# top_level.net
KiCad netlist of a schematic drawn in Altium Designer
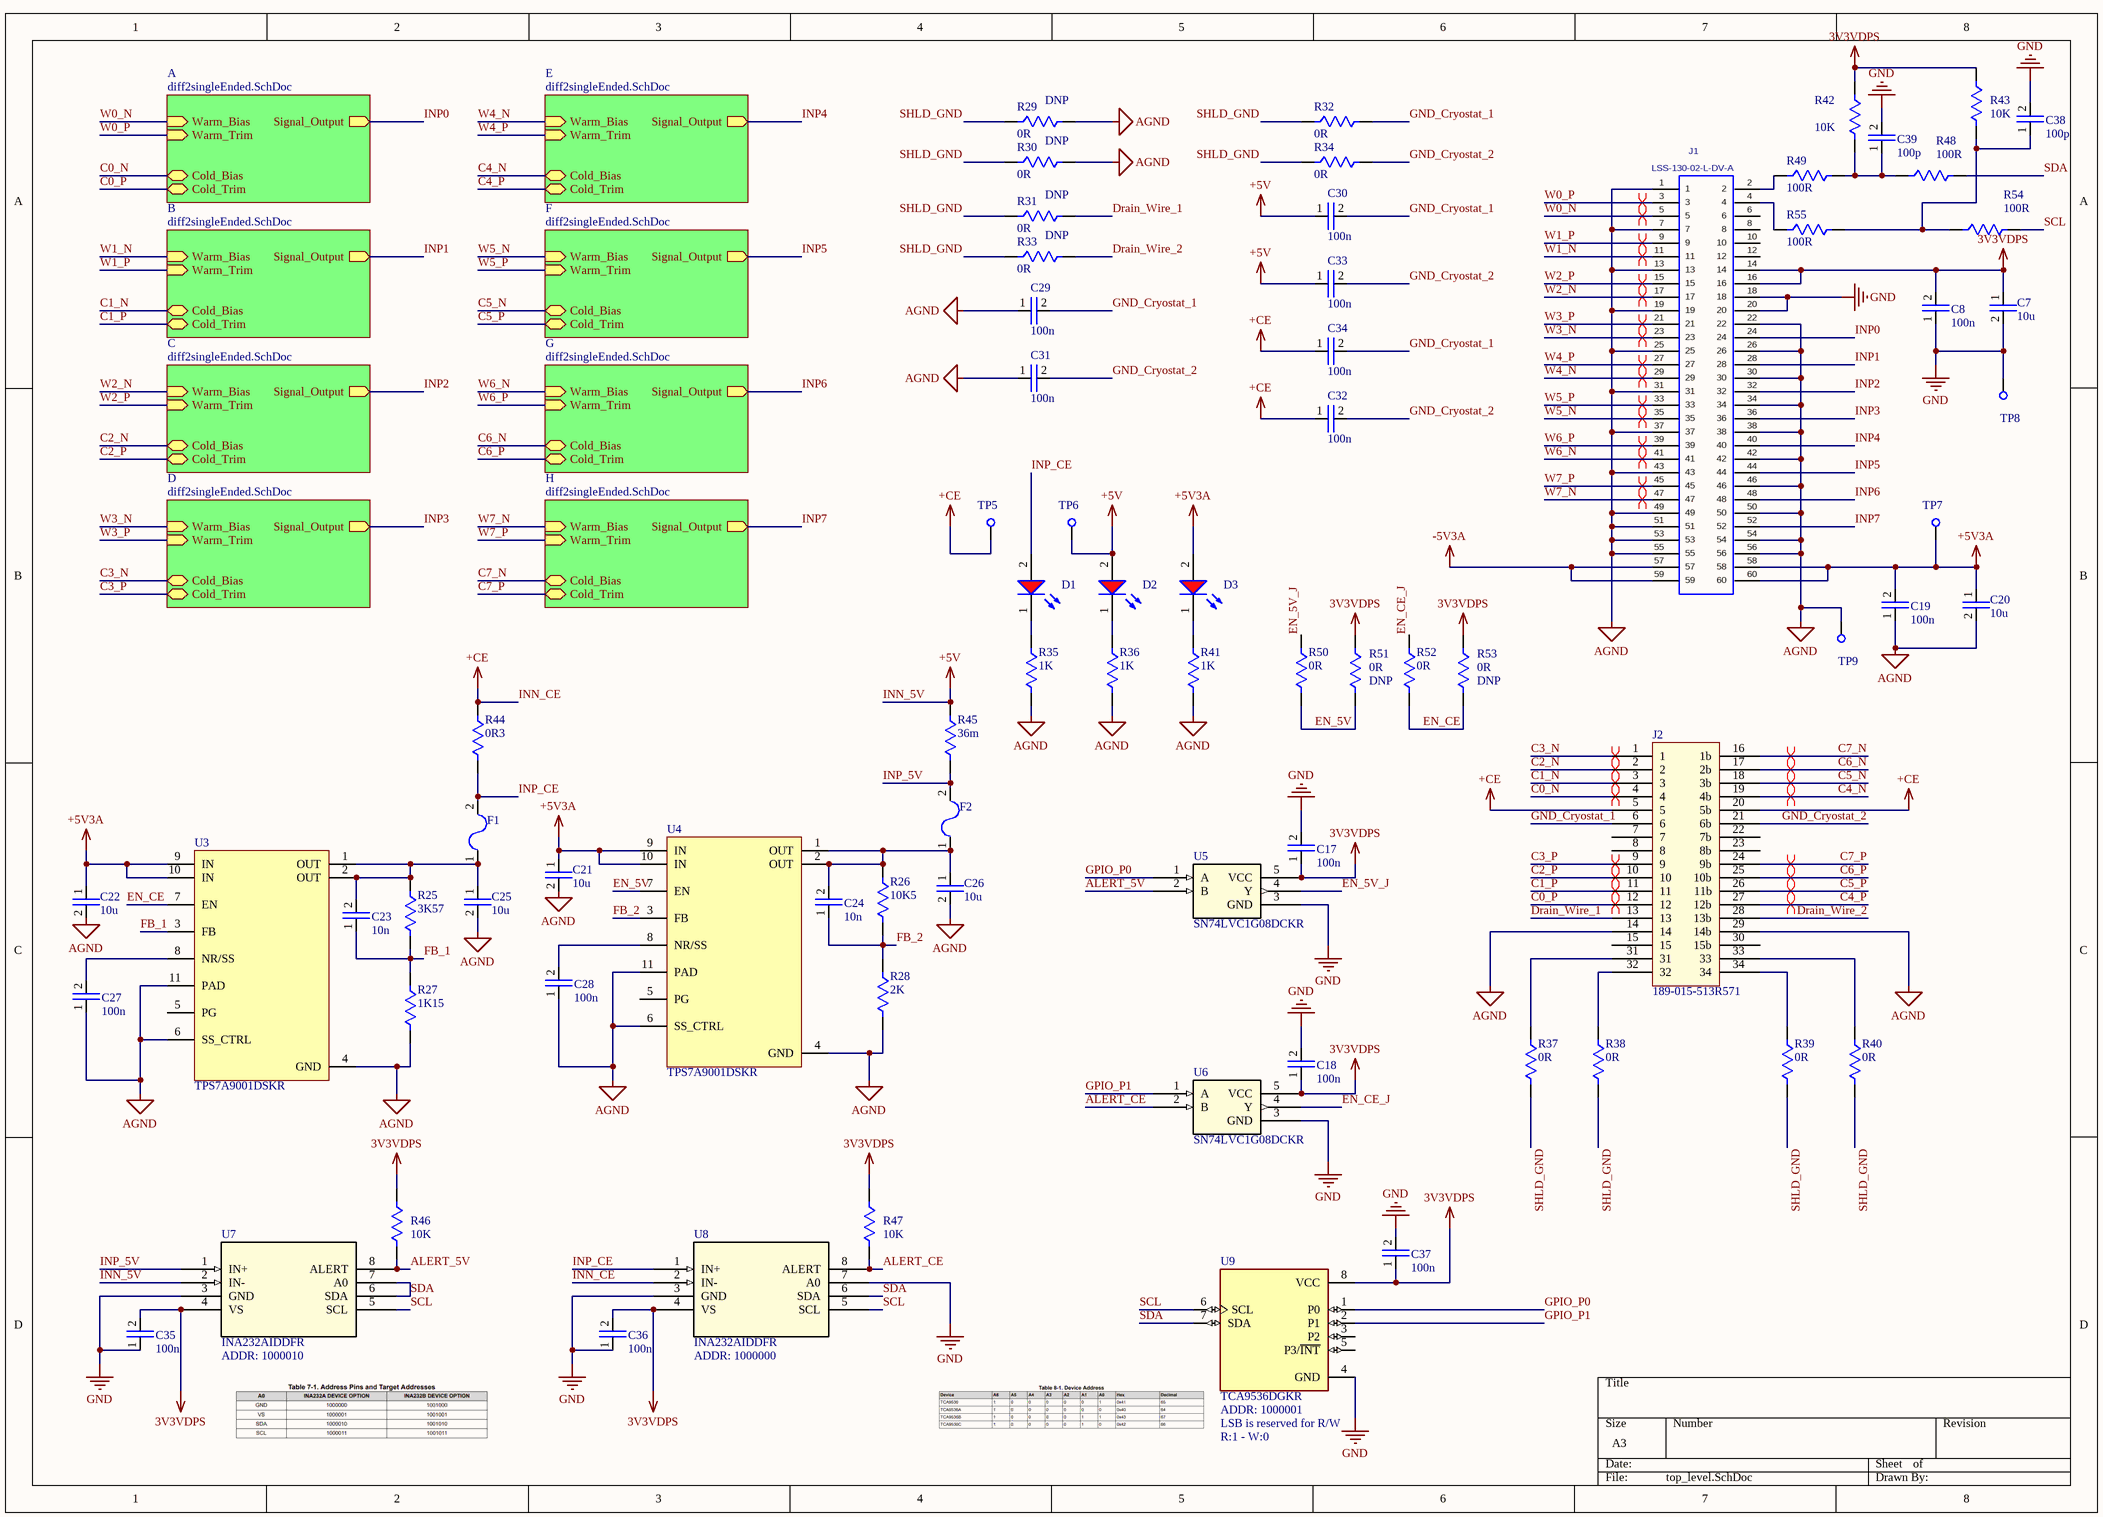
[diagram p0: top_level.SchDoc]

(export (version "E")
  (design (tool "Eeschema 10.0.6"))
  (components
    (comp (ref "C7")
      (value "10u")
      (footprint "CAPC3216X190N")
      (description "10 µF ±10% 100V Ceramic Capacitor X6S 1206 (3216 Metric)")
      (fields (field (name "MP") "C3216X6S2A106K160AC"))
      (libsource (lib "ChipCapacitor_1206") (part "Capacitor"))
    )
    (comp (ref "C8")
      (value "100n")
      (footprint "CAPC1608X09N")
      (description "0.1 µF ±10% 100V Ceramic Capacitor X7R 0603 (1608 Metric)")
      (fields (field (name "MP") "CC0603KRX7R0BB104"))
      (libsource (lib "Capacitor_0603") (part "Capacitor"))
    )
    (comp (ref "C17")
      (value "100n")
      (footprint "CAPC1608X09N")
      (description "0.1 µF ±10% 100V Ceramic Capacitor X7R 0603 (1608 Metric)")
      (fields (field (name "MP") "CC0603KRX7R0BB104"))
      (libsource (lib "Capacitor_0603") (part "Capacitor"))
    )
    (comp (ref "C18")
      (value "100n")
      (footprint "CAPC1608X09N")
      (description "0.1 µF ±10% 100V Ceramic Capacitor X7R 0603 (1608 Metric)")
      (fields (field (name "MP") "CC0603KRX7R0BB104"))
      (libsource (lib "Capacitor_0603") (part "Capacitor"))
    )
    (comp (ref "C19")
      (value "100n")
      (footprint "CAPC1608X09N")
      (description "0.1 µF ±10% 100V Ceramic Capacitor X7R 0603 (1608 Metric)")
      (fields (field (name "MP") "CC0603KRX7R0BB104"))
      (libsource (lib "Capacitor_0603") (part "Capacitor"))
    )
    (comp (ref "C20")
      (value "10u")
      (footprint "CAPC3216X190N")
      (description "10 µF ±10% 100V Ceramic Capacitor X6S 1206 (3216 Metric)")
      (fields (field (name "MP") "C3216X6S2A106K160AC"))
      (libsource (lib "ChipCapacitor_1206") (part "Capacitor"))
    )
    (comp (ref "C21")
      (value "10u")
      (footprint "CAPC3216X190N")
      (description "10 µF ±10% 100V Ceramic Capacitor X6S 1206 (3216 Metric)")
      (fields (field (name "MP") "C3216X6S2A106K160AC"))
      (libsource (lib "ChipCapacitor_1206") (part "Capacitor"))
    )
    (comp (ref "C22")
      (value "10u")
      (footprint "CAPC3216X190N")
      (description "10 µF ±10% 100V Ceramic Capacitor X6S 1206 (3216 Metric)")
      (fields (field (name "MP") "C3216X6S2A106K160AC"))
      (libsource (lib "ChipCapacitor_1206") (part "Capacitor"))
    )
    (comp (ref "C23")
      (value "10n")
      (footprint "CAPC1608X09N")
      (description "10000 pF ±10% 50V Ceramic Capacitor X7R 0603 (1608 Metric)")
      (fields (field (name "MP") "0603B103K500CT"))
      (libsource (lib "Capacitor_0603") (part "Capacitor"))
    )
    (comp (ref "C24")
      (value "10n")
      (footprint "CAPC1608X09N")
      (description "10000 pF ±10% 50V Ceramic Capacitor X7R 0603 (1608 Metric)")
      (fields (field (name "MP") "0603B103K500CT"))
      (libsource (lib "Capacitor_0603") (part "Capacitor"))
    )
    (comp (ref "C25")
      (value "10u")
      (footprint "CAPC3216X190N")
      (description "10 µF ±10% 100V Ceramic Capacitor X6S 1206 (3216 Metric)")
      (fields (field (name "MP") "C3216X6S2A106K160AC"))
      (libsource (lib "ChipCapacitor_1206") (part "Capacitor"))
    )
    (comp (ref "C26")
      (value "10u")
      (footprint "CAPC3216X190N")
      (description "10 µF ±10% 100V Ceramic Capacitor X6S 1206 (3216 Metric)")
      (fields (field (name "MP") "C3216X6S2A106K160AC"))
      (libsource (lib "ChipCapacitor_1206") (part "Capacitor"))
    )
    (comp (ref "C27")
      (value "100n")
      (footprint "CAPC1608X09N")
      (description "0.1 µF ±10% 100V Ceramic Capacitor X7R 0603 (1608 Metric)")
      (fields (field (name "MP") "CC0603KRX7R0BB104"))
      (libsource (lib "Capacitor_0603") (part "Capacitor"))
    )
    (comp (ref "C28")
      (value "100n")
      (footprint "CAPC1608X09N")
      (description "0.1 µF ±10% 100V Ceramic Capacitor X7R 0603 (1608 Metric)")
      (fields (field (name "MP") "CC0603KRX7R0BB104"))
      (libsource (lib "Capacitor_0603") (part "Capacitor"))
    )
    (comp (ref "C29")
      (value "100n")
      (footprint "CAPC1608X09N")
      (description "0.1 µF ±10% 100V Ceramic Capacitor X7R 0603 (1608 Metric)")
      (fields (field (name "MP") "CC0603KRX7R0BB104"))
      (libsource (lib "Capacitor_0603") (part "Capacitor"))
    )
    (comp (ref "C30")
      (value "100n")
      (footprint "CAPC1608X09N")
      (description "0.1 µF ±10% 100V Ceramic Capacitor X7R 0603 (1608 Metric)")
      (fields (field (name "MP") "CC0603KRX7R0BB104"))
      (libsource (lib "Capacitor_0603") (part "Capacitor"))
    )
    (comp (ref "C31")
      (value "100n")
      (footprint "CAPC1608X09N")
      (description "0.1 µF ±10% 100V Ceramic Capacitor X7R 0603 (1608 Metric)")
      (fields (field (name "MP") "CC0603KRX7R0BB104"))
      (libsource (lib "Capacitor_0603") (part "Capacitor"))
    )
    (comp (ref "C32")
      (value "100n")
      (footprint "CAPC1608X09N")
      (description "0.1 µF ±10% 100V Ceramic Capacitor X7R 0603 (1608 Metric)")
      (fields (field (name "MP") "CC0603KRX7R0BB104"))
      (libsource (lib "Capacitor_0603") (part "Capacitor"))
    )
    (comp (ref "C33")
      (value "100n")
      (footprint "CAPC1608X09N")
      (description "0.1 µF ±10% 100V Ceramic Capacitor X7R 0603 (1608 Metric)")
      (fields (field (name "MP") "CC0603KRX7R0BB104"))
      (libsource (lib "Capacitor_0603") (part "Capacitor"))
    )
    (comp (ref "C34")
      (value "100n")
      (footprint "CAPC1608X09N")
      (description "0.1 µF ±10% 100V Ceramic Capacitor X7R 0603 (1608 Metric)")
      (fields (field (name "MP") "CC0603KRX7R0BB104"))
      (libsource (lib "Capacitor_0603") (part "Capacitor"))
    )
    (comp (ref "C35")
      (value "100n")
      (footprint "CAPC1608X09N")
      (description "0.1 µF ±10% 100V Ceramic Capacitor X7R 0603 (1608 Metric)")
      (fields (field (name "MP") "CC0603KRX7R0BB104"))
      (libsource (lib "Capacitor_0603") (part "Capacitor"))
    )
    (comp (ref "C36")
      (value "100n")
      (footprint "CAPC1608X09N")
      (description "0.1 µF ±10% 100V Ceramic Capacitor X7R 0603 (1608 Metric)")
      (fields (field (name "MP") "CC0603KRX7R0BB104"))
      (libsource (lib "Capacitor_0603") (part "Capacitor"))
    )
    (comp (ref "C37")
      (value "100n")
      (footprint "CAPC1608X09N")
      (description "0.1 µF ±10% 100V Ceramic Capacitor X7R 0603 (1608 Metric)")
      (fields (field (name "MP") "CC0603KRX7R0BB104"))
      (libsource (lib "Capacitor_0603") (part "Capacitor"))
    )
    (comp (ref "C38")
      (value "100p")
      (footprint "CAPC1608X09N")
      (description "100 pF ±5% 50V Ceramic Capacitor C0G, NP0 0603 (1608 Metric)")
      (fields (field (name "MP") "GRM1885C1H101JA01D"))
      (libsource (lib "Capacitor_0603") (part "Capacitor"))
    )
    (comp (ref "C39")
      (value "100p")
      (footprint "CAPC1608X09N")
      (description "100 pF ±5% 50V Ceramic Capacitor C0G, NP0 0603 (1608 Metric)")
      (fields (field (name "MP") "GRM1885C1H101JA01D"))
      (libsource (lib "Capacitor_0603") (part "Capacitor"))
    )
    (comp (ref "D1")
      (value "150060RS75000")
      (footprint "WL-SMCW_0603_150060xx75000")
      (description "WL-SMCW Mono-color Chip LED Waterclear, SMT, size 0603, Red, 2V, 140°")
      (fields (field (name "MANUFACTURER") "Wurth Elektronik"))
      (libsource (lib "Altium_WL-SMCW_rev22d") (part "150060RS75000"))
    )
    (comp (ref "D2")
      (value "150060RS75000")
      (footprint "WL-SMCW_0603_150060xx75000")
      (description "WL-SMCW Mono-color Chip LED Waterclear, SMT, size 0603, Red, 2V, 140°")
      (fields (field (name "MANUFACTURER") "Wurth Elektronik"))
      (libsource (lib "Altium_WL-SMCW_rev22d") (part "150060RS75000"))
    )
    (comp (ref "D3")
      (value "150060RS75000")
      (footprint "WL-SMCW_0603_150060xx75000")
      (description "WL-SMCW Mono-color Chip LED Waterclear, SMT, size 0603, Red, 2V, 140°")
      (fields (field (name "MANUFACTURER") "Wurth Elektronik"))
      (libsource (lib "Altium_WL-SMCW_rev22d") (part "150060RS75000"))
    )
    (comp (ref "F1")
      (value "F0603G0R20FNTR")
      (footprint "RESC1608X08N")
      (description "200 mA AC 32 V DC Fuse Board Mount (Cartridge Style Excluded) Surface Mount 0603 (1608 Metric)")
      (libsource (lib "F0603G0R20FNTR") (part "Fuse"))
    )
    (comp (ref "F2")
      (value "F0603G0R20FNTR")
      (footprint "RESC1608X08N")
      (description "200 mA AC 32 V DC Fuse Board Mount (Cartridge Style Excluded) Surface Mount 0603 (1608 Metric)")
      (libsource (lib "F0603G0R20FNTR") (part "Fuse"))
    )
    (comp (ref "J1")
      (value "LSS-130-02-L-DV-A")
      (footprint "LSS-130-XX-XX-DV-A")
      (description "0.635MM TERMINAL/SOCKET COMB, 60 PINS.")
      (fields (field (name "MANUFACTURER") "SAMTEC") (field (name "CREATED") "May 11, 2015 - Wendy Xin"))
      (libsource (lib "LSS-130-XX-XX-DV-A--Symbol-Altium-44987") (part "LSS-130-XX-XX-DV-A"))
    )
    (comp (ref "J2")
      (value "189-015-513R571")
      (footprint "189-015-513R571")
      (description "15, 15 Position D-Sub - Stacked Receptacle, Female Sockets Connector")
      (libsource (lib "189_015_513R571") (part "189-015-513R571"))
    )
    (comp (ref "R25")
      (value "3K57")
      (footprint "RESC1608X55N")
      (description "3.57 kOhms ±1% 0.1W, 1/10W Chip Resistor 0603 (1608 Metric) Automotive AEC-Q200 Thick Film")
      (fields (field (name "MP") "RMCF0603FT3K57"))
      (libsource (lib "ChipResistor_0603") (part "Resistor"))
    )
    (comp (ref "R26")
      (value "10K5")
      (footprint "RESC1608X55N")
      (description "10.5 kOhms ±1% 0.1W, 1/10W Chip Resistor 0603 (1608 Metric) Automotive AEC-Q200 Thick Film")
      (fields (field (name "MP") "RMCF0603FT10K5"))
      (libsource (lib "ChipResistor_0603") (part "Resistor"))
    )
    (comp (ref "R27")
      (value "1K15")
      (footprint "RESC1608X55N")
      (description "1.15 kOhms ±1% 0.1W, 1/10W Chip Resistor 0603 (1608 Metric) Automotive AEC-Q200 Thick Film")
      (fields (field (name "MP") "RMCF0603FT1K15"))
      (libsource (lib "ChipResistor_0603") (part "Resistor"))
    )
    (comp (ref "R28")
      (value "2K")
      (footprint "RESC1608X55N")
      (description "2 kOhms ±1% 0.1W, 1/10W Chip Resistor 0603 (1608 Metric) Automotive AEC-Q200 Thick Film")
      (fields (field (name "MP") "ERJ-3EKF2001V"))
      (libsource (lib "ChipResistor_0603") (part "Resistor"))
    )
    (comp (ref "R29")
      (value "DNP")
      (footprint "RESC1608X55N")
      (description "0 Ohms Jumper Chip Resistor 0603 (1608 Metric) Automotive AEC-Q200 Thick Film")
      (fields (field (name "ALTIUM_VALUE") "0R") (field (name "MP") "RMCF0603ZT0R00"))
      (libsource (lib "ChipResistor_0603") (part "Resistor"))
    )
    (comp (ref "R30")
      (value "DNP")
      (footprint "RESC1608X55N")
      (description "0 Ohms Jumper Chip Resistor 0603 (1608 Metric) Automotive AEC-Q200 Thick Film")
      (fields (field (name "ALTIUM_VALUE") "0R") (field (name "MP") "RMCF0603ZT0R00"))
      (libsource (lib "ChipResistor_0603") (part "Resistor"))
    )
    (comp (ref "R31")
      (value "DNP")
      (footprint "RESC1608X55N")
      (description "0 Ohms Jumper Chip Resistor 0603 (1608 Metric) Automotive AEC-Q200 Thick Film")
      (fields (field (name "ALTIUM_VALUE") "0R") (field (name "MP") "RMCF0603ZT0R00"))
      (libsource (lib "ChipResistor_0603") (part "Resistor"))
    )
    (comp (ref "R32")
      (value "0R")
      (footprint "RESC1608X55N")
      (description "0 Ohms Jumper Chip Resistor 0603 (1608 Metric) Automotive AEC-Q200 Thick Film")
      (fields (field (name "MP") "RMCF0603ZT0R00"))
      (libsource (lib "ChipResistor_0603") (part "Resistor"))
    )
    (comp (ref "R33")
      (value "DNP")
      (footprint "RESC1608X55N")
      (description "0 Ohms Jumper Chip Resistor 0603 (1608 Metric) Automotive AEC-Q200 Thick Film")
      (fields (field (name "ALTIUM_VALUE") "0R") (field (name "MP") "RMCF0603ZT0R00"))
      (libsource (lib "ChipResistor_0603") (part "Resistor"))
    )
    (comp (ref "R34")
      (value "0R")
      (footprint "RESC1608X55N")
      (description "0 Ohms Jumper Chip Resistor 0603 (1608 Metric) Automotive AEC-Q200 Thick Film")
      (fields (field (name "MP") "RMCF0603ZT0R00"))
      (libsource (lib "ChipResistor_0603") (part "Resistor"))
    )
    (comp (ref "R35")
      (value "1K")
      (footprint "RESC1608X55N")
      (description "1 kOhms ±0.1% 0.1W, 1/10W Chip Resistor 0603 (1608 Metric) Thin Film")
      (fields (field (name "MP") "RT0603BRD071KL"))
      (libsource (lib "ChipResistor_0603") (part "Resistor"))
    )
    (comp (ref "R36")
      (value "1K")
      (footprint "RESC1608X55N")
      (description "1 kOhms ±0.1% 0.1W, 1/10W Chip Resistor 0603 (1608 Metric) Thin Film")
      (fields (field (name "MP") "RT0603BRD071KL"))
      (libsource (lib "ChipResistor_0603") (part "Resistor"))
    )
    (comp (ref "R37")
      (value "0R")
      (footprint "RESC1608X55N")
      (description "0 Ohms Jumper Chip Resistor 0603 (1608 Metric) Automotive AEC-Q200 Thick Film")
      (fields (field (name "MP") "RMCF0603ZT0R00"))
      (libsource (lib "ChipResistor_0603") (part "Resistor"))
    )
    (comp (ref "R38")
      (value "0R")
      (footprint "RESC1608X55N")
      (description "0 Ohms Jumper Chip Resistor 0603 (1608 Metric) Automotive AEC-Q200 Thick Film")
      (fields (field (name "MP") "RMCF0603ZT0R00"))
      (libsource (lib "ChipResistor_0603") (part "Resistor"))
    )
    (comp (ref "R39")
      (value "0R")
      (footprint "RESC1608X55N")
      (description "0 Ohms Jumper Chip Resistor 0603 (1608 Metric) Automotive AEC-Q200 Thick Film")
      (fields (field (name "MP") "RMCF0603ZT0R00"))
      (libsource (lib "ChipResistor_0603") (part "Resistor"))
    )
    (comp (ref "R40")
      (value "0R")
      (footprint "RESC1608X55N")
      (description "0 Ohms Jumper Chip Resistor 0603 (1608 Metric) Automotive AEC-Q200 Thick Film")
      (fields (field (name "MP") "RMCF0603ZT0R00"))
      (libsource (lib "ChipResistor_0603") (part "Resistor"))
    )
    (comp (ref "R41")
      (value "1K")
      (footprint "RESC1608X55N")
      (description "1 kOhms ±0.1% 0.1W, 1/10W Chip Resistor 0603 (1608 Metric) Thin Film")
      (fields (field (name "MP") "RT0603BRD071KL"))
      (libsource (lib "ChipResistor_0603") (part "Resistor"))
    )
    (comp (ref "R42")
      (value "10K")
      (footprint "RESC1608X55N")
      (description "10 kOhms ±1% 0.1W, 1/10W Chip Resistor 0603 (1608 Metric) Moisture Resistant Thick Film")
      (fields (field (name "MP") "RC0603FR-0710KL"))
      (libsource (lib "ChipResistor_0603") (part "Resistor"))
    )
    (comp (ref "R43")
      (value "10K")
      (footprint "RESC1608X55N")
      (description "10 kOhms ±1% 0.1W, 1/10W Chip Resistor 0603 (1608 Metric) Moisture Resistant Thick Film")
      (fields (field (name "MP") "RC0603FR-0710KL"))
      (libsource (lib "ChipResistor_0603") (part "Resistor"))
    )
    (comp (ref "R44")
      (value "0R3")
      (footprint "RESC1608X55N")
      (description "300 mOhms ±1% 0.1W, 1/10W Chip Resistor 0603 (1608 Metric) Automotive AEC-Q200 Thick Film")
      (fields (field (name "MP") "ERJ-3RQFR30V"))
      (libsource (lib "ChipResistor_0603") (part "Resistor"))
    )
    (comp (ref "R45")
      (value "36m")
      (footprint "RESC1608X55N")
      (fields (field (name "MP") "ERJ-3BWFR036V"))
      (libsource (lib "ChipResistor_0603") (part "Resistor"))
    )
    (comp (ref "R46")
      (value "10K")
      (footprint "RESC1608X55N")
      (description "10 kOhms ±1% 0.1W, 1/10W Chip Resistor 0603 (1608 Metric) Moisture Resistant Thick Film")
      (fields (field (name "MP") "RC0603FR-0710KL"))
      (libsource (lib "ChipResistor_0603") (part "Resistor"))
    )
    (comp (ref "R47")
      (value "10K")
      (footprint "RESC1608X55N")
      (description "10 kOhms ±1% 0.1W, 1/10W Chip Resistor 0603 (1608 Metric) Moisture Resistant Thick Film")
      (fields (field (name "MP") "RC0603FR-0710KL"))
      (libsource (lib "ChipResistor_0603") (part "Resistor"))
    )
    (comp (ref "R48")
      (value "100R")
      (footprint "RESC1608X55N")
      (description "100 Ohms ±1% 0.1W, 1/10W Chip Resistor 0603 (1608 Metric) Moisture Resistant Thick Film")
      (fields (field (name "MP") "RC0603FR-07100RL"))
      (libsource (lib "ChipResistor_0603") (part "Resistor"))
    )
    (comp (ref "R49")
      (value "100R")
      (footprint "RESC1608X55N")
      (description "100 Ohms ±1% 0.1W, 1/10W Chip Resistor 0603 (1608 Metric) Moisture Resistant Thick Film")
      (fields (field (name "MP") "RC0603FR-07100RL"))
      (libsource (lib "ChipResistor_0603") (part "Resistor"))
    )
    (comp (ref "R50")
      (value "0R")
      (footprint "RESC1608X55N")
      (description "0 Ohms Jumper Chip Resistor 0603 (1608 Metric) Automotive AEC-Q200 Thick Film")
      (fields (field (name "MP") "RMCF0603ZT0R00"))
      (libsource (lib "ChipResistor_0603") (part "Resistor"))
    )
    (comp (ref "R51")
      (value "DNP")
      (footprint "RESC1608X55N")
      (description "0 Ohms Jumper Chip Resistor 0603 (1608 Metric) Automotive AEC-Q200 Thick Film")
      (fields (field (name "ALTIUM_VALUE") "0R") (field (name "MP") "RMCF0603ZT0R00"))
      (libsource (lib "ChipResistor_0603") (part "Resistor"))
    )
    (comp (ref "R52")
      (value "0R")
      (footprint "RESC1608X55N")
      (description "0 Ohms Jumper Chip Resistor 0603 (1608 Metric) Automotive AEC-Q200 Thick Film")
      (fields (field (name "MP") "RMCF0603ZT0R00"))
      (libsource (lib "ChipResistor_0603") (part "Resistor"))
    )
    (comp (ref "R53")
      (value "DNP")
      (footprint "RESC1608X55N")
      (description "0 Ohms Jumper Chip Resistor 0603 (1608 Metric) Automotive AEC-Q200 Thick Film")
      (fields (field (name "ALTIUM_VALUE") "0R") (field (name "MP") "RMCF0603ZT0R00"))
      (libsource (lib "ChipResistor_0603") (part "Resistor"))
    )
    (comp (ref "R54")
      (value "100R")
      (footprint "RESC1608X55N")
      (description "100 Ohms ±1% 0.1W, 1/10W Chip Resistor 0603 (1608 Metric) Moisture Resistant Thick Film")
      (fields (field (name "MP") "RC0603FR-07100RL"))
      (libsource (lib "ChipResistor_0603") (part "Resistor"))
    )
    (comp (ref "R55")
      (value "100R")
      (footprint "RESC1608X55N")
      (description "100 Ohms ±1% 0.1W, 1/10W Chip Resistor 0603 (1608 Metric) Moisture Resistant Thick Film")
      (fields (field (name "MP") "RC0603FR-07100RL"))
      (libsource (lib "ChipResistor_0603") (part "Resistor"))
    )
    (comp (ref "TP5")
      (value "testPoint_throughHole")
      (footprint "testPoint_ThroughHole")
      (libsource (lib "testPoint") (part "testPoint_throughHole"))
    )
    (comp (ref "TP6")
      (value "testPoint_throughHole")
      (footprint "testPoint_ThroughHole")
      (libsource (lib "testPoint") (part "testPoint_throughHole"))
    )
    (comp (ref "TP7")
      (value "testPoint_throughHole")
      (footprint "testPoint_ThroughHole")
      (libsource (lib "testPoint") (part "testPoint_throughHole"))
    )
    (comp (ref "TP8")
      (value "testPoint_throughHole")
      (footprint "testPoint_ThroughHole")
      (libsource (lib "testPoint") (part "testPoint_throughHole"))
    )
    (comp (ref "TP9")
      (value "testPoint_throughHole")
      (footprint "testPoint_ThroughHole")
      (libsource (lib "testPoint") (part "testPoint_throughHole"))
    )
    (comp (ref "U3")
      (value "TPS7A9001DSKR")
      (footprint "SON50P250X250X80-11N")
      (fields (field (name "MF") "Texas Instruments"))
      (libsource (lib "TPS7A9001DSKR") (part "TPS7A9001DSKR"))
    )
    (comp (ref "U4")
      (value "TPS7A9001DSKR")
      (footprint "SON50P250X250X80-11N")
      (fields (field (name "MF") "Texas Instruments"))
      (libsource (lib "TPS7A9001DSKR") (part "TPS7A9001DSKR"))
    )
    (comp (ref "U5")
      (value "SN74LVC1G08DCKR")
      (footprint "DCK5")
      (description "AND Gate IC 1 Channel SC-70-5")
      (libsource (lib "SN74LVC1G08DCKR") (part "SN74LVC1G08DCKR"))
    )
    (comp (ref "U6")
      (value "SN74LVC1G08DCKR")
      (footprint "DCK5")
      (description "AND Gate IC 1 Channel SC-70-5")
      (libsource (lib "SN74LVC1G08DCKR") (part "SN74LVC1G08DCKR"))
    )
    (comp (ref "U7")
      (value "INA232AIDDFR")
      (footprint "SOT_32AIDDFR_TEX")
      (description "Current Monitor Regulator High/Low-Side TSOT-23-8")
      (libsource (lib "INA232AIDDFR") (part "INA232AIDDFR"))
    )
    (comp (ref "U8")
      (value "INA232AIDDFR")
      (footprint "SOT_32AIDDFR_TEX")
      (description "Current Monitor Regulator High/Low-Side TSOT-23-8")
      (libsource (lib "INA232AIDDFR") (part "INA232AIDDFR"))
    )
    (comp (ref "U9")
      (value "TCA9536DGKR")
      (footprint "SOP65P490X110-8N")
      (description "Remote 4-Bit IÂ²C and SMBus I/O expander with configuration registers")
      (fields (field (name "MF") "Texas Instruments"))
      (libsource (lib "TCA9536DGKR") (part "TCA9536DGKR"))
    )
  )
  (nets
    (net (code "1") (name "+5V") (class "Default")
      (node (ref "C30") (pin "1") (pinfunction "2_1") (pintype "passive"))
      (node (ref "C33") (pin "1") (pinfunction "2_1") (pintype "passive"))
      (node (ref "D2") (pin "2") (pinfunction "A_2") (pintype "passive"))
      (node (ref "R45") (pin "2") (pinfunction "2_2") (pintype "passive"))
      (node (ref "TP6") (pin "0") (pintype "passive"))
      (node (ref "U7") (pin "2") (pinfunction "IN-_2") (pintype "input"))
    )
    (net (code "2") (name "+5V3A") (class "Default")
      (node (ref "C19") (pin "2") (pinfunction "2_2") (pintype "passive"))
      (node (ref "C20") (pin "1") (pinfunction "2_1") (pintype "passive"))
      (node (ref "C21") (pin "1") (pinfunction "2_1") (pintype "passive"))
      (node (ref "C22") (pin "1") (pinfunction "2_1") (pintype "passive"))
      (node (ref "D3") (pin "2") (pinfunction "A_2") (pintype "passive"))
      (node (ref "J1") (pin "58") (pinfunction "58_58") (pintype "passive"))
      (node (ref "J1") (pin "60") (pinfunction "60_60") (pintype "passive"))
      (node (ref "TP7") (pin "0") (pintype "passive"))
      (node (ref "U3") (pin "10") (pinfunction "IN_10") (pintype "passive"))
      (node (ref "U3") (pin "9") (pinfunction "IN_9") (pintype "passive"))
      (node (ref "U4") (pin "10") (pinfunction "IN_10") (pintype "passive"))
      (node (ref "U4") (pin "9") (pinfunction "IN_9") (pintype "passive"))
    )
    (net (code "3") (name "+CE") (class "Default")
      (node (ref "C32") (pin "1") (pinfunction "2_1") (pintype "passive"))
      (node (ref "C34") (pin "1") (pinfunction "2_1") (pintype "passive"))
      (node (ref "J2") (pin "20") (pinfunction "5b_20") (pintype "passive"))
      (node (ref "J2") (pin "5") (pinfunction "5_5") (pintype "passive"))
      (node (ref "R44") (pin "2") (pinfunction "2_2") (pintype "passive"))
      (node (ref "TP5") (pin "0") (pintype "passive"))
      (node (ref "U8") (pin "2") (pinfunction "IN-_2") (pintype "input"))
    )
    (net (code "4") (name "-5V3A") (class "Default")
      (node (ref "J1") (pin "57") (pinfunction "57_57") (pintype "passive"))
      (node (ref "J1") (pin "59") (pinfunction "59_59") (pintype "passive"))
    )
    (net (code "5") (name "/ALERT_5V") (class "Default")
      (node (ref "R46") (pin "1") (pinfunction "1_1") (pintype "passive"))
      (node (ref "U5") (pin "2") (pinfunction "B_2") (pintype "input"))
      (node (ref "U7") (pin "8") (pinfunction "ALERT_8") (pintype "passive"))
    )
    (net (code "6") (name "/ALERT_CE") (class "Default")
      (node (ref "R47") (pin "1") (pinfunction "1_1") (pintype "passive"))
      (node (ref "U6") (pin "2") (pinfunction "B_2") (pintype "input"))
      (node (ref "U8") (pin "8") (pinfunction "ALERT_8") (pintype "passive"))
    )
    (net (code "7") (name "/C0_N") (class "Default")
      (node (ref "J2") (pin "4") (pinfunction "4_4") (pintype "passive"))
    )
    (net (code "8") (name "/C0_P") (class "Default")
      (node (ref "J2") (pin "12") (pinfunction "12_12") (pintype "passive"))
    )
    (net (code "9") (name "/C1_N") (class "Default")
      (node (ref "J2") (pin "3") (pinfunction "3_3") (pintype "passive"))
    )
    (net (code "10") (name "/C1_P") (class "Default")
      (node (ref "J2") (pin "11") (pinfunction "11_11") (pintype "passive"))
    )
    (net (code "11") (name "/C2_N") (class "Default")
      (node (ref "J2") (pin "2") (pinfunction "2_2") (pintype "passive"))
    )
    (net (code "12") (name "/C2_P") (class "Default")
      (node (ref "J2") (pin "10") (pinfunction "10_10") (pintype "passive"))
    )
    (net (code "13") (name "/C3_N") (class "Default")
      (node (ref "J2") (pin "1") (pinfunction "1_1") (pintype "passive"))
    )
    (net (code "14") (name "/C3_P") (class "Default")
      (node (ref "J2") (pin "9") (pinfunction "9_9") (pintype "passive"))
    )
    (net (code "15") (name "/C4_N") (class "Default")
      (node (ref "J2") (pin "19") (pinfunction "4b_19") (pintype "passive"))
    )
    (net (code "16") (name "/C4_P") (class "Default")
      (node (ref "J2") (pin "27") (pinfunction "12b_27") (pintype "passive"))
    )
    (net (code "17") (name "/C5_N") (class "Default")
      (node (ref "J2") (pin "18") (pinfunction "3b_18") (pintype "passive"))
    )
    (net (code "18") (name "/C5_P") (class "Default")
      (node (ref "J2") (pin "26") (pinfunction "11b_26") (pintype "passive"))
    )
    (net (code "19") (name "/C6_N") (class "Default")
      (node (ref "J2") (pin "17") (pinfunction "2b_17") (pintype "passive"))
    )
    (net (code "20") (name "/C6_P") (class "Default")
      (node (ref "J2") (pin "25") (pinfunction "10b_25") (pintype "passive"))
    )
    (net (code "21") (name "/C7_N") (class "Default")
      (node (ref "J2") (pin "16") (pinfunction "1b_16") (pintype "passive"))
    )
    (net (code "22") (name "/C7_P") (class "Default")
      (node (ref "J2") (pin "24") (pinfunction "9b_24") (pintype "passive"))
    )
    (net (code "23") (name "/Drain_Wire_1") (class "Default")
      (node (ref "J2") (pin "13") (pinfunction "13_13") (pintype "passive"))
      (node (ref "R31") (pin "1") (pinfunction "1_1") (pintype "passive"))
    )
    (net (code "24") (name "/Drain_Wire_2") (class "Default")
      (node (ref "J2") (pin "28") (pinfunction "13b_28") (pintype "passive"))
      (node (ref "R33") (pin "1") (pinfunction "1_1") (pintype "passive"))
    )
    (net (code "25") (name "/EN_5V") (class "Default")
      (node (ref "R50") (pin "1") (pinfunction "1_1") (pintype "passive"))
      (node (ref "R51") (pin "1") (pinfunction "1_1") (pintype "passive"))
      (node (ref "U4") (pin "7") (pinfunction "EN_7") (pintype "passive"))
    )
    (net (code "26") (name "/EN_5V_J") (class "Default")
      (node (ref "R50") (pin "2") (pinfunction "2_2") (pintype "passive"))
      (node (ref "U5") (pin "4") (pinfunction "Y_4") (pintype "output"))
    )
    (net (code "27") (name "/EN_CE") (class "Default")
      (node (ref "R52") (pin "1") (pinfunction "1_1") (pintype "passive"))
      (node (ref "R53") (pin "1") (pinfunction "1_1") (pintype "passive"))
      (node (ref "U3") (pin "7") (pinfunction "EN_7") (pintype "passive"))
    )
    (net (code "28") (name "/EN_CE_J") (class "Default")
      (node (ref "R52") (pin "2") (pinfunction "2_2") (pintype "passive"))
      (node (ref "U6") (pin "4") (pinfunction "Y_4") (pintype "output"))
    )
    (net (code "29") (name "/FB_1") (class "Default")
      (node (ref "C23") (pin "1") (pinfunction "2_1") (pintype "passive"))
      (node (ref "R25") (pin "1") (pinfunction "1_1") (pintype "passive"))
      (node (ref "R27") (pin "2") (pinfunction "2_2") (pintype "passive"))
      (node (ref "U3") (pin "3") (pinfunction "FB_3") (pintype "passive"))
    )
    (net (code "30") (name "/FB_2") (class "Default")
      (node (ref "C24") (pin "1") (pinfunction "2_1") (pintype "passive"))
      (node (ref "R26") (pin "1") (pinfunction "1_1") (pintype "passive"))
      (node (ref "R28") (pin "2") (pinfunction "2_2") (pintype "passive"))
      (node (ref "U4") (pin "3") (pinfunction "FB_3") (pintype "passive"))
    )
    (net (code "31") (name "/GND_Cryostat_1") (class "Default")
      (node (ref "C29") (pin "2") (pinfunction "2_2") (pintype "passive"))
      (node (ref "C30") (pin "2") (pinfunction "2_2") (pintype "passive"))
      (node (ref "C34") (pin "2") (pinfunction "2_2") (pintype "passive"))
      (node (ref "J2") (pin "6") (pinfunction "6_6") (pintype "passive"))
      (node (ref "R32") (pin "1") (pinfunction "1_1") (pintype "passive"))
    )
    (net (code "32") (name "/GND_Cryostat_2") (class "Default")
      (node (ref "C31") (pin "2") (pinfunction "2_2") (pintype "passive"))
      (node (ref "C32") (pin "2") (pinfunction "2_2") (pintype "passive"))
      (node (ref "C33") (pin "2") (pinfunction "2_2") (pintype "passive"))
      (node (ref "J2") (pin "21") (pinfunction "6b_21") (pintype "passive"))
      (node (ref "R34") (pin "1") (pinfunction "1_1") (pintype "passive"))
    )
    (net (code "33") (name "/GPIO_P0") (class "Default")
      (node (ref "U5") (pin "1") (pinfunction "A_1") (pintype "input"))
      (node (ref "U9") (pin "1") (pinfunction "P0_1") (pintype "bidirectional"))
    )
    (net (code "34") (name "/GPIO_P1") (class "Default")
      (node (ref "U6") (pin "1") (pinfunction "A_1") (pintype "input"))
      (node (ref "U9") (pin "2") (pinfunction "P1_2") (pintype "bidirectional"))
    )
    (net (code "35") (name "/INP0") (class "Default")
      (node (ref "J1") (pin "24") (pinfunction "24_24") (pintype "passive"))
    )
    (net (code "36") (name "/INP1") (class "Default")
      (node (ref "J1") (pin "28") (pinfunction "28_28") (pintype "passive"))
    )
    (net (code "37") (name "/INP2") (class "Default")
      (node (ref "J1") (pin "32") (pinfunction "32_32") (pintype "passive"))
    )
    (net (code "38") (name "/INP3") (class "Default")
      (node (ref "J1") (pin "36") (pinfunction "36_36") (pintype "passive"))
    )
    (net (code "39") (name "/INP4") (class "Default")
      (node (ref "J1") (pin "40") (pinfunction "40_40") (pintype "passive"))
    )
    (net (code "40") (name "/INP5") (class "Default")
      (node (ref "J1") (pin "44") (pinfunction "44_44") (pintype "passive"))
    )
    (net (code "41") (name "/INP6") (class "Default")
      (node (ref "J1") (pin "48") (pinfunction "48_48") (pintype "passive"))
    )
    (net (code "42") (name "/INP7") (class "Default")
      (node (ref "J1") (pin "52") (pinfunction "52_52") (pintype "passive"))
    )
    (net (code "43") (name "/INP_5V") (class "Default")
      (node (ref "F2") (pin "2") (pinfunction "2_2") (pintype "passive"))
      (node (ref "R45") (pin "1") (pinfunction "1_1") (pintype "passive"))
      (node (ref "U7") (pin "1") (pinfunction "IN+_1") (pintype "input"))
    )
    (net (code "44") (name "/INP_CE") (class "Default")
      (node (ref "D1") (pin "2") (pinfunction "A_2") (pintype "passive"))
      (node (ref "F1") (pin "2") (pinfunction "2_2") (pintype "passive"))
      (node (ref "R44") (pin "1") (pinfunction "1_1") (pintype "passive"))
      (node (ref "U8") (pin "1") (pinfunction "IN+_1") (pintype "input"))
    )
    (net (code "45") (name "/SCL") (class "Default")
      (node (ref "R54") (pin "1") (pinfunction "1_1") (pintype "passive"))
      (node (ref "U7") (pin "5") (pinfunction "SCL_5") (pintype "passive"))
      (node (ref "U8") (pin "5") (pinfunction "SCL_5") (pintype "passive"))
      (node (ref "U9") (pin "6") (pinfunction "SCL_6") (pintype "bidirectional"))
    )
    (net (code "46") (name "/SDA") (class "Default")
      (node (ref "R48") (pin "1") (pinfunction "1_1") (pintype "passive"))
      (node (ref "U7") (pin "6") (pinfunction "SDA_6") (pintype "passive"))
      (node (ref "U7") (pin "7") (pinfunction "A0_7") (pintype "passive"))
      (node (ref "U8") (pin "6") (pinfunction "SDA_6") (pintype "passive"))
      (node (ref "U9") (pin "7") (pinfunction "SDA_7") (pintype "bidirectional"))
    )
    (net (code "47") (name "/SHLD_GND") (class "Default")
      (node (ref "R29") (pin "2") (pinfunction "2_2") (pintype "passive"))
      (node (ref "R30") (pin "2") (pinfunction "2_2") (pintype "passive"))
      (node (ref "R31") (pin "2") (pinfunction "2_2") (pintype "passive"))
      (node (ref "R32") (pin "2") (pinfunction "2_2") (pintype "passive"))
      (node (ref "R33") (pin "2") (pinfunction "2_2") (pintype "passive"))
      (node (ref "R34") (pin "2") (pinfunction "2_2") (pintype "passive"))
      (node (ref "R37") (pin "1") (pinfunction "1_1") (pintype "passive"))
      (node (ref "R38") (pin "1") (pinfunction "1_1") (pintype "passive"))
      (node (ref "R39") (pin "1") (pinfunction "1_1") (pintype "passive"))
      (node (ref "R40") (pin "1") (pinfunction "1_1") (pintype "passive"))
    )
    (net (code "48") (name "/W0_N") (class "Default")
      (node (ref "J1") (pin "5") (pinfunction "5_5") (pintype "passive"))
    )
    (net (code "49") (name "/W0_P") (class "Default")
      (node (ref "J1") (pin "3") (pinfunction "3_3") (pintype "passive"))
    )
    (net (code "50") (name "/W1_N") (class "Default")
      (node (ref "J1") (pin "11") (pinfunction "11_11") (pintype "passive"))
    )
    (net (code "51") (name "/W1_P") (class "Default")
      (node (ref "J1") (pin "9") (pinfunction "9_9") (pintype "passive"))
    )
    (net (code "52") (name "/W2_N") (class "Default")
      (node (ref "J1") (pin "17") (pinfunction "17_17") (pintype "passive"))
    )
    (net (code "53") (name "/W2_P") (class "Default")
      (node (ref "J1") (pin "15") (pinfunction "15_15") (pintype "passive"))
    )
    (net (code "54") (name "/W3_N") (class "Default")
      (node (ref "J1") (pin "23") (pinfunction "23_23") (pintype "passive"))
    )
    (net (code "55") (name "/W3_P") (class "Default")
      (node (ref "J1") (pin "21") (pinfunction "21_21") (pintype "passive"))
    )
    (net (code "56") (name "/W4_N") (class "Default")
      (node (ref "J1") (pin "29") (pinfunction "29_29") (pintype "passive"))
    )
    (net (code "57") (name "/W4_P") (class "Default")
      (node (ref "J1") (pin "27") (pinfunction "27_27") (pintype "passive"))
    )
    (net (code "58") (name "/W5_N") (class "Default")
      (node (ref "J1") (pin "35") (pinfunction "35_35") (pintype "passive"))
    )
    (net (code "59") (name "/W5_P") (class "Default")
      (node (ref "J1") (pin "33") (pinfunction "33_33") (pintype "passive"))
    )
    (net (code "60") (name "/W6_N") (class "Default")
      (node (ref "J1") (pin "41") (pinfunction "41_41") (pintype "passive"))
    )
    (net (code "61") (name "/W6_P") (class "Default")
      (node (ref "J1") (pin "39") (pinfunction "39_39") (pintype "passive"))
    )
    (net (code "62") (name "/W7_N") (class "Default")
      (node (ref "J1") (pin "47") (pinfunction "47_47") (pintype "passive"))
    )
    (net (code "63") (name "/W7_P") (class "Default")
      (node (ref "J1") (pin "45") (pinfunction "45_45") (pintype "passive"))
    )
    (net (code "64") (name "3V3VDPS") (class "Default")
      (node (ref "C17") (pin "1") (pinfunction "2_1") (pintype "passive"))
      (node (ref "C18") (pin "1") (pinfunction "2_1") (pintype "passive"))
      (node (ref "C35") (pin "2") (pinfunction "2_2") (pintype "passive"))
      (node (ref "C36") (pin "2") (pinfunction "2_2") (pintype "passive"))
      (node (ref "C37") (pin "1") (pinfunction "2_1") (pintype "passive"))
      (node (ref "C7") (pin "1") (pinfunction "2_1") (pintype "passive"))
      (node (ref "C8") (pin "2") (pinfunction "2_2") (pintype "passive"))
      (node (ref "J1") (pin "14") (pinfunction "14_14") (pintype "passive"))
      (node (ref "J1") (pin "16") (pinfunction "16_16") (pintype "passive"))
      (node (ref "R42") (pin "2") (pinfunction "2_2") (pintype "passive"))
      (node (ref "R43") (pin "2") (pinfunction "2_2") (pintype "passive"))
      (node (ref "R46") (pin "2") (pinfunction "2_2") (pintype "passive"))
      (node (ref "R47") (pin "2") (pinfunction "2_2") (pintype "passive"))
      (node (ref "R51") (pin "2") (pinfunction "2_2") (pintype "passive"))
      (node (ref "R53") (pin "2") (pinfunction "2_2") (pintype "passive"))
      (node (ref "U5") (pin "5") (pinfunction "VCC_5") (pintype "power_in"))
      (node (ref "U6") (pin "5") (pinfunction "VCC_5") (pintype "power_in"))
      (node (ref "U7") (pin "4") (pinfunction "VS_4") (pintype "passive"))
      (node (ref "U8") (pin "4") (pinfunction "VS_4") (pintype "passive"))
      (node (ref "U9") (pin "8") (pinfunction "VCC_8") (pintype "power_in"))
    )
    (net (code "65") (name "AGND") (class "Default")
      (node (ref "C19") (pin "1") (pinfunction "2_1") (pintype "passive"))
      (node (ref "C20") (pin "2") (pinfunction "2_2") (pintype "passive"))
      (node (ref "C21") (pin "2") (pinfunction "2_2") (pintype "passive"))
      (node (ref "C22") (pin "2") (pinfunction "2_2") (pintype "passive"))
      (node (ref "C25") (pin "2") (pinfunction "2_2") (pintype "passive"))
      (node (ref "C26") (pin "2") (pinfunction "2_2") (pintype "passive"))
      (node (ref "C27") (pin "1") (pinfunction "2_1") (pintype "passive"))
      (node (ref "C28") (pin "1") (pinfunction "2_1") (pintype "passive"))
      (node (ref "C29") (pin "1") (pinfunction "2_1") (pintype "passive"))
      (node (ref "C31") (pin "1") (pinfunction "2_1") (pintype "passive"))
      (node (ref "J1") (pin "1") (pinfunction "1_1") (pintype "passive"))
      (node (ref "J1") (pin "13") (pinfunction "13_13") (pintype "passive"))
      (node (ref "J1") (pin "19") (pinfunction "19_19") (pintype "passive"))
      (node (ref "J1") (pin "22") (pinfunction "22_22") (pintype "passive"))
      (node (ref "J1") (pin "25") (pinfunction "25_25") (pintype "passive"))
      (node (ref "J1") (pin "26") (pinfunction "26_26") (pintype "passive"))
      (node (ref "J1") (pin "30") (pinfunction "30_30") (pintype "passive"))
      (node (ref "J1") (pin "31") (pinfunction "31_31") (pintype "passive"))
      (node (ref "J1") (pin "34") (pinfunction "34_34") (pintype "passive"))
      (node (ref "J1") (pin "37") (pinfunction "37_37") (pintype "passive"))
      (node (ref "J1") (pin "38") (pinfunction "38_38") (pintype "passive"))
      (node (ref "J1") (pin "42") (pinfunction "42_42") (pintype "passive"))
      (node (ref "J1") (pin "43") (pinfunction "43_43") (pintype "passive"))
      (node (ref "J1") (pin "46") (pinfunction "46_46") (pintype "passive"))
      (node (ref "J1") (pin "49") (pinfunction "49_49") (pintype "passive"))
      (node (ref "J1") (pin "50") (pinfunction "50_50") (pintype "passive"))
      (node (ref "J1") (pin "51") (pinfunction "51_51") (pintype "passive"))
      (node (ref "J1") (pin "53") (pinfunction "53_53") (pintype "passive"))
      (node (ref "J1") (pin "54") (pinfunction "54_54") (pintype "passive"))
      (node (ref "J1") (pin "55") (pinfunction "55_55") (pintype "passive"))
      (node (ref "J1") (pin "56") (pinfunction "56_56") (pintype "passive"))
      (node (ref "J1") (pin "7") (pinfunction "7_7") (pintype "passive"))
      (node (ref "J2") (pin "14") (pinfunction "14_14") (pintype "passive"))
      (node (ref "J2") (pin "29") (pinfunction "14b_29") (pintype "passive"))
      (node (ref "R27") (pin "1") (pinfunction "1_1") (pintype "passive"))
      (node (ref "R28") (pin "1") (pinfunction "1_1") (pintype "passive"))
      (node (ref "R29") (pin "1") (pinfunction "1_1") (pintype "passive"))
      (node (ref "R30") (pin "1") (pinfunction "1_1") (pintype "passive"))
      (node (ref "R35") (pin "1") (pinfunction "1_1") (pintype "passive"))
      (node (ref "R36") (pin "1") (pinfunction "1_1") (pintype "passive"))
      (node (ref "R41") (pin "1") (pinfunction "1_1") (pintype "passive"))
      (node (ref "TP9") (pin "0") (pintype "passive"))
      (node (ref "U3") (pin "11") (pinfunction "PAD_11") (pintype "passive"))
      (node (ref "U3") (pin "4") (pinfunction "GND_4") (pintype "passive"))
      (node (ref "U3") (pin "6") (pinfunction "SS_CTRL_6") (pintype "passive"))
      (node (ref "U4") (pin "11") (pinfunction "PAD_11") (pintype "passive"))
      (node (ref "U4") (pin "4") (pinfunction "GND_4") (pintype "passive"))
      (node (ref "U4") (pin "6") (pinfunction "SS_CTRL_6") (pintype "passive"))
    )
    (net (code "66") (name "GND") (class "Default")
      (node (ref "C17") (pin "2") (pinfunction "2_2") (pintype "passive"))
      (node (ref "C18") (pin "2") (pinfunction "2_2") (pintype "passive"))
      (node (ref "C35") (pin "1") (pinfunction "2_1") (pintype "passive"))
      (node (ref "C36") (pin "1") (pinfunction "2_1") (pintype "passive"))
      (node (ref "C37") (pin "2") (pinfunction "2_2") (pintype "passive"))
      (node (ref "C38") (pin "2") (pinfunction "2_2") (pintype "passive"))
      (node (ref "C39") (pin "2") (pinfunction "2_2") (pintype "passive"))
      (node (ref "C7") (pin "2") (pinfunction "2_2") (pintype "passive"))
      (node (ref "C8") (pin "1") (pinfunction "2_1") (pintype "passive"))
      (node (ref "J1") (pin "18") (pinfunction "18_18") (pintype "passive"))
      (node (ref "J1") (pin "20") (pinfunction "20_20") (pintype "passive"))
      (node (ref "TP8") (pin "0") (pintype "passive"))
      (node (ref "U5") (pin "3") (pinfunction "GND_3") (pintype "power_in"))
      (node (ref "U6") (pin "3") (pinfunction "GND_3") (pintype "power_in"))
      (node (ref "U7") (pin "3") (pinfunction "GND_3") (pintype "power_in"))
      (node (ref "U8") (pin "3") (pinfunction "GND_3") (pintype "power_in"))
      (node (ref "U8") (pin "7") (pinfunction "A0_7") (pintype "passive"))
      (node (ref "U9") (pin "4") (pinfunction "GND_4") (pintype "power_in"))
    )
    (net (code "67") (name "Net-(C23-Pad2)") (class "Default")
      (node (ref "C23") (pin "2") (pinfunction "2_2") (pintype "passive"))
      (node (ref "C25") (pin "1") (pinfunction "2_1") (pintype "passive"))
      (node (ref "F1") (pin "1") (pinfunction "1_1") (pintype "passive"))
      (node (ref "R25") (pin "2") (pinfunction "2_2") (pintype "passive"))
      (node (ref "U3") (pin "1") (pinfunction "OUT_1") (pintype "passive"))
      (node (ref "U3") (pin "2") (pinfunction "OUT_2") (pintype "passive"))
    )
    (net (code "68") (name "Net-(C24-Pad2)") (class "Default")
      (node (ref "C24") (pin "2") (pinfunction "2_2") (pintype "passive"))
      (node (ref "C26") (pin "1") (pinfunction "2_1") (pintype "passive"))
      (node (ref "F2") (pin "1") (pinfunction "1_1") (pintype "passive"))
      (node (ref "R26") (pin "2") (pinfunction "2_2") (pintype "passive"))
      (node (ref "U4") (pin "1") (pinfunction "OUT_1") (pintype "passive"))
      (node (ref "U4") (pin "2") (pinfunction "OUT_2") (pintype "passive"))
    )
    (net (code "69") (name "Net-(C38-2-Pad1)") (class "Default")
      (node (ref "C38") (pin "1") (pinfunction "2_1") (pintype "passive"))
      (node (ref "R43") (pin "1") (pinfunction "1_1") (pintype "passive"))
      (node (ref "R54") (pin "2") (pinfunction "2_2") (pintype "passive"))
      (node (ref "R55") (pin "1") (pinfunction "1_1") (pintype "passive"))
    )
    (net (code "70") (name "Net-(C39-2-Pad1)") (class "Default")
      (node (ref "C39") (pin "1") (pinfunction "2_1") (pintype "passive"))
      (node (ref "R42") (pin "1") (pinfunction "1_1") (pintype "passive"))
      (node (ref "R48") (pin "2") (pinfunction "2_2") (pintype "passive"))
      (node (ref "R49") (pin "1") (pinfunction "1_1") (pintype "passive"))
    )
    (net (code "71") (name "Net-(D1-K)") (class "Default")
      (node (ref "D1") (pin "1") (pinfunction "K_1") (pintype "passive"))
      (node (ref "R35") (pin "2") (pinfunction "2_2") (pintype "passive"))
    )
    (net (code "72") (name "Net-(D2-K)") (class "Default")
      (node (ref "D2") (pin "1") (pinfunction "K_1") (pintype "passive"))
      (node (ref "R36") (pin "2") (pinfunction "2_2") (pintype "passive"))
    )
    (net (code "73") (name "Net-(D3-K)") (class "Default")
      (node (ref "D3") (pin "1") (pinfunction "K_1") (pintype "passive"))
      (node (ref "R41") (pin "2") (pinfunction "2_2") (pintype "passive"))
    )
    (net (code "74") (name "Net-(J1-Pad2)") (class "Default")
      (node (ref "J1") (pin "2") (pinfunction "2_2") (pintype "passive"))
      (node (ref "R49") (pin "2") (pinfunction "2_2") (pintype "passive"))
    )
    (net (code "75") (name "Net-(J1-Pad4)") (class "Default")
      (node (ref "J1") (pin "4") (pinfunction "4_4") (pintype "passive"))
      (node (ref "R55") (pin "2") (pinfunction "2_2") (pintype "passive"))
    )
    (net (code "76") (name "Net-(J2-Pad31)") (class "Default")
      (node (ref "J2") (pin "31") (pinfunction "31_31") (pintype "passive"))
      (node (ref "R37") (pin "2") (pinfunction "2_2") (pintype "passive"))
    )
    (net (code "77") (name "Net-(J2-Pad32)") (class "Default")
      (node (ref "J2") (pin "32") (pinfunction "32_32") (pintype "passive"))
      (node (ref "R38") (pin "2") (pinfunction "2_2") (pintype "passive"))
    )
    (net (code "78") (name "Net-(J2-Pad33)") (class "Default")
      (node (ref "J2") (pin "33") (pinfunction "33_33") (pintype "passive"))
      (node (ref "R40") (pin "2") (pinfunction "2_2") (pintype "passive"))
    )
    (net (code "79") (name "Net-(J2-Pad34)") (class "Default")
      (node (ref "J2") (pin "34") (pinfunction "34_34") (pintype "passive"))
      (node (ref "R39") (pin "2") (pinfunction "2_2") (pintype "passive"))
    )
    (net (code "80") (name "Net-(U3-NR{slash}SS)") (class "Default")
      (node (ref "C27") (pin "2") (pinfunction "2_2") (pintype "passive"))
      (node (ref "U3") (pin "8") (pinfunction "NR/SS_8") (pintype "passive"))
    )
    (net (code "81") (name "Net-(U4-NR{slash}SS)") (class "Default")
      (node (ref "C28") (pin "2") (pinfunction "2_2") (pintype "passive"))
      (node (ref "U4") (pin "8") (pinfunction "NR/SS_8") (pintype "passive"))
    )
    (net (code "82") (name "unconnected-(J1-Pad6)") (class "Default")
      (node (ref "J1") (pin "6") (pinfunction "6_6") (pintype "passive"))
    )
    (net (code "83") (name "unconnected-(J1-Pad8)") (class "Default")
      (node (ref "J1") (pin "8") (pinfunction "8_8") (pintype "passive"))
    )
    (net (code "84") (name "unconnected-(J1-Pad10)") (class "Default")
      (node (ref "J1") (pin "10") (pinfunction "10_10") (pintype "passive"))
    )
    (net (code "85") (name "unconnected-(J1-Pad12)") (class "Default")
      (node (ref "J1") (pin "12") (pinfunction "12_12") (pintype "passive"))
    )
    (net (code "86") (name "unconnected-(J2-7b-Pad22)") (class "Default")
      (node (ref "J2") (pin "22") (pinfunction "7b_22") (pintype "passive"))
    )
    (net (code "87") (name "unconnected-(J2-8b-Pad23)") (class "Default")
      (node (ref "J2") (pin "23") (pinfunction "8b_23") (pintype "passive"))
    )
    (net (code "88") (name "unconnected-(J2-15b-Pad30)") (class "Default")
      (node (ref "J2") (pin "30") (pinfunction "15b_30") (pintype "passive"))
    )
    (net (code "89") (name "unconnected-(J2-Pad7)") (class "Default")
      (node (ref "J2") (pin "7") (pinfunction "7_7") (pintype "passive"))
    )
    (net (code "90") (name "unconnected-(J2-Pad8)") (class "Default")
      (node (ref "J2") (pin "8") (pinfunction "8_8") (pintype "passive"))
    )
    (net (code "91") (name "unconnected-(J2-Pad15)") (class "Default")
      (node (ref "J2") (pin "15") (pinfunction "15_15") (pintype "passive"))
    )
    (net (code "92") (name "unconnected-(U3-PG-Pad5)") (class "Default")
      (node (ref "U3") (pin "5") (pinfunction "PG_5") (pintype "passive"))
    )
    (net (code "93") (name "unconnected-(U4-PG-Pad5)") (class "Default")
      (node (ref "U4") (pin "5") (pinfunction "PG_5") (pintype "passive"))
    )
    (net (code "94") (name "unconnected-(U9-P2-Pad3)") (class "Default")
      (node (ref "U9") (pin "3") (pinfunction "P2_3") (pintype "bidirectional"))
    )
    (net (code "95") (name "unconnected-(U9-P3{slash}~{INT}-Pad5)") (class "Default")
      (node (ref "U9") (pin "5") (pinfunction "P3/~{INT}_5") (pintype "bidirectional"))
    )
  )
)
